# APD9328_FPGA_SUPPLY.net
KiCad netlist of a schematic drawn in Altium Designer
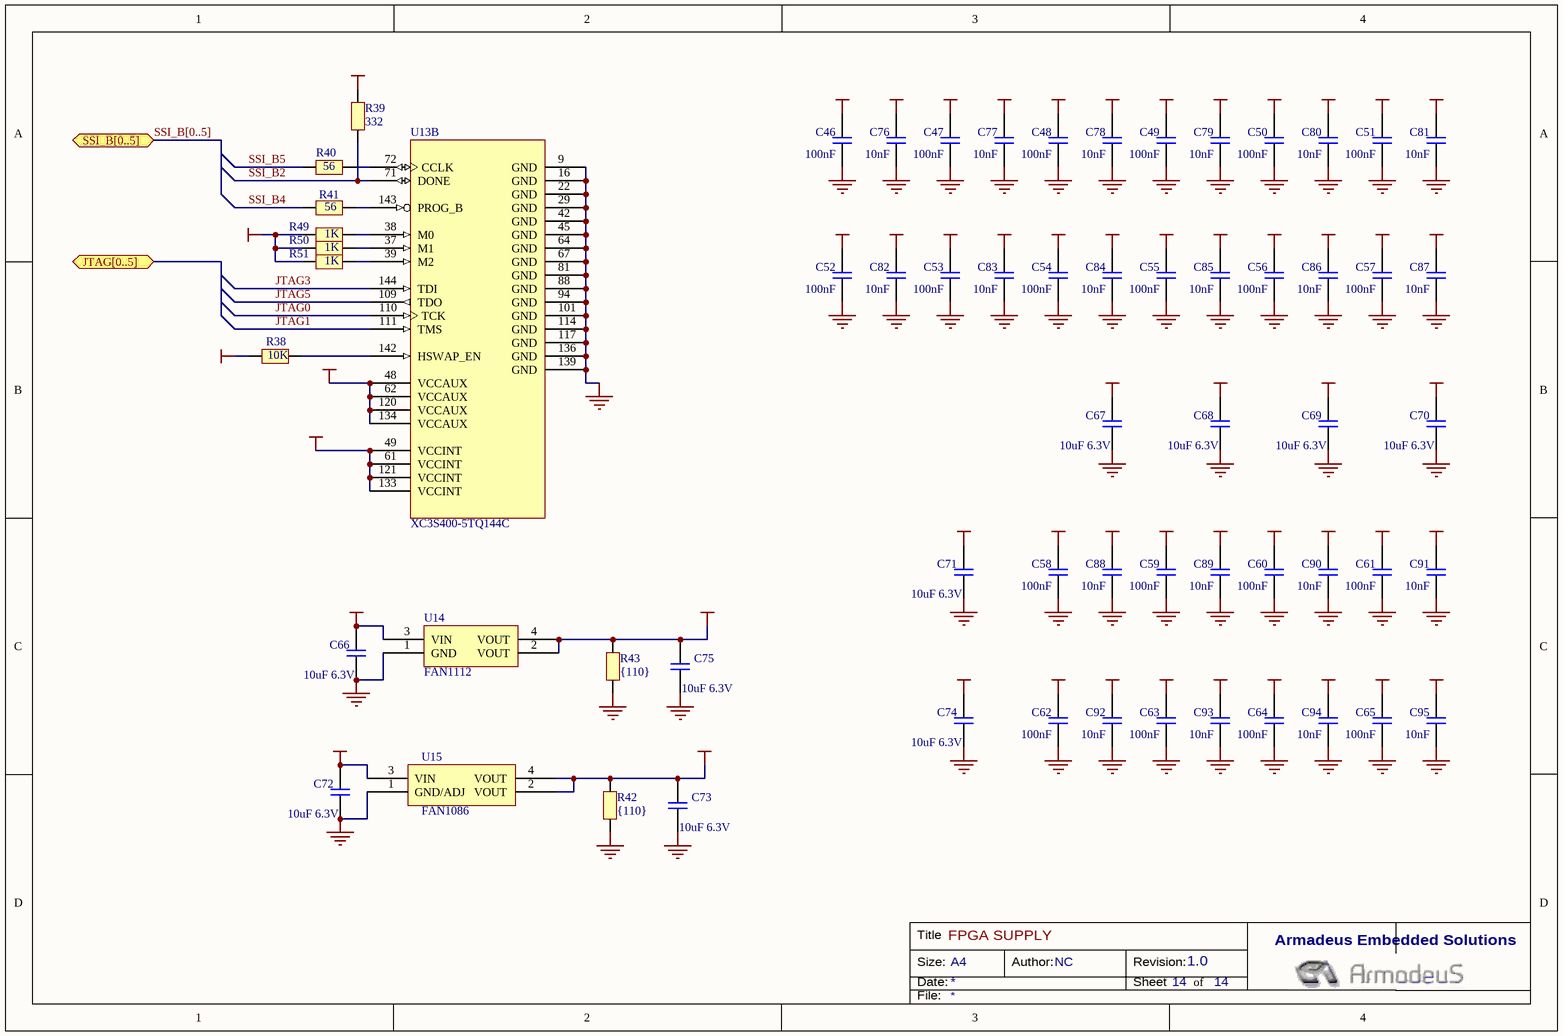
[diagram p0: APD9328_FPGA_SUPPLY.SchDoc]

(export (version "E")
  (design (tool "Eeschema 10.0.6"))
  (components
    (comp (ref "C46") (value "100nF") (footprint "0402") (libsource (lib "*") (part "Cap")))
    (comp (ref "C47") (value "100nF") (footprint "0402") (libsource (lib "*") (part "Cap")))
    (comp (ref "C48") (value "100nF") (footprint "0402") (libsource (lib "*") (part "Cap")))
    (comp (ref "C49") (value "100nF") (footprint "0402") (libsource (lib "*") (part "Cap")))
    (comp (ref "C50") (value "100nF") (footprint "0402") (libsource (lib "*") (part "Cap")))
    (comp (ref "C51") (value "100nF") (footprint "0402") (libsource (lib "*") (part "Cap")))
    (comp (ref "C52") (value "100nF") (footprint "0402") (libsource (lib "*") (part "Cap")))
    (comp (ref "C53") (value "100nF") (footprint "0402") (libsource (lib "*") (part "Cap")))
    (comp (ref "C54") (value "100nF") (footprint "0402") (libsource (lib "*") (part "Cap")))
    (comp (ref "C55") (value "100nF") (footprint "0402") (libsource (lib "*") (part "Cap")))
    (comp (ref "C56") (value "100nF") (footprint "0402") (libsource (lib "*") (part "Cap")))
    (comp (ref "C57") (value "100nF") (footprint "0402") (libsource (lib "*") (part "Cap")))
    (comp (ref "C58") (value "100nF") (footprint "0402") (libsource (lib "*") (part "Cap")))
    (comp (ref "C59") (value "100nF") (footprint "0402") (libsource (lib "*") (part "Cap")))
    (comp (ref "C60") (value "100nF") (footprint "0402") (libsource (lib "*") (part "Cap")))
    (comp (ref "C61") (value "100nF") (footprint "0402") (libsource (lib "*") (part "Cap")))
    (comp (ref "C62") (value "100nF") (footprint "0402") (libsource (lib "*") (part "Cap")))
    (comp (ref "C63") (value "100nF") (footprint "0402") (libsource (lib "*") (part "Cap")))
    (comp (ref "C64") (value "100nF") (footprint "0402") (libsource (lib "*") (part "Cap")))
    (comp (ref "C65") (value "100nF") (footprint "0402") (libsource (lib "*") (part "Cap")))
    (comp (ref "C66")
      (value "10uF 6.3V")
      (footprint "0805")
      (description "Ceramic Capacitor")
      (libsource (lib "*") (part "Cap"))
    )
    (comp (ref "C67")
      (value "10uF 6.3V")
      (footprint "0805")
      (description "Ceramic Capacitor")
      (libsource (lib "*") (part "Cap"))
    )
    (comp (ref "C68")
      (value "10uF 6.3V")
      (footprint "0805")
      (description "Ceramic Capacitor")
      (libsource (lib "*") (part "Cap"))
    )
    (comp (ref "C69")
      (value "10uF 6.3V")
      (footprint "0805")
      (description "Ceramic Capacitor")
      (libsource (lib "*") (part "Cap"))
    )
    (comp (ref "C70")
      (value "10uF 6.3V")
      (footprint "0805")
      (description "Ceramic Capacitor")
      (libsource (lib "*") (part "Cap"))
    )
    (comp (ref "C71")
      (value "10uF 6.3V")
      (footprint "0805")
      (description "Ceramic Capacitor")
      (libsource (lib "*") (part "Cap"))
    )
    (comp (ref "C72")
      (value "10uF 6.3V")
      (footprint "0805")
      (description "Ceramic Capacitor")
      (libsource (lib "*") (part "Cap"))
    )
    (comp (ref "C73")
      (value "10uF 6.3V")
      (footprint "0805")
      (description "Ceramic Capacitor")
      (libsource (lib "*") (part "Cap"))
    )
    (comp (ref "C74")
      (value "10uF 6.3V")
      (footprint "0805")
      (description "Ceramic Capacitor")
      (libsource (lib "*") (part "Cap"))
    )
    (comp (ref "C75")
      (value "10uF 6.3V")
      (footprint "0805")
      (description "Ceramic Capacitor")
      (libsource (lib "*") (part "Cap"))
    )
    (comp (ref "C76")
      (value "10nF")
      (footprint "0402")
      (fields (field (name "MANUFACTURER") "Kemet") (field (name "PART NUMBER") "C0402C103K4RACTU"))
      (libsource (lib "*") (part "Cap"))
    )
    (comp (ref "C77") (value "10nF") (footprint "0402") (libsource (lib "*") (part "Cap")))
    (comp (ref "C78") (value "10nF") (footprint "0402") (libsource (lib "*") (part "Cap")))
    (comp (ref "C79") (value "10nF") (footprint "0402") (libsource (lib "*") (part "Cap")))
    (comp (ref "C80") (value "10nF") (footprint "0402") (libsource (lib "*") (part "Cap")))
    (comp (ref "C81") (value "10nF") (footprint "0402") (libsource (lib "*") (part "Cap")))
    (comp (ref "C82") (value "10nF") (footprint "0402") (libsource (lib "*") (part "Cap")))
    (comp (ref "C83") (value "10nF") (footprint "0402") (libsource (lib "*") (part "Cap")))
    (comp (ref "C84") (value "10nF") (footprint "0402") (libsource (lib "*") (part "Cap")))
    (comp (ref "C85") (value "10nF") (footprint "0402") (libsource (lib "*") (part "Cap")))
    (comp (ref "C86") (value "10nF") (footprint "0402") (libsource (lib "*") (part "Cap")))
    (comp (ref "C87") (value "10nF") (footprint "0402") (libsource (lib "*") (part "Cap")))
    (comp (ref "C88") (value "10nF") (footprint "0402") (libsource (lib "*") (part "Cap")))
    (comp (ref "C89") (value "10nF") (footprint "0402") (libsource (lib "*") (part "Cap")))
    (comp (ref "C90") (value "10nF") (footprint "0402") (libsource (lib "*") (part "Cap")))
    (comp (ref "C91") (value "10nF") (footprint "0402") (libsource (lib "*") (part "Cap")))
    (comp (ref "C92") (value "10nF") (footprint "0402") (libsource (lib "*") (part "Cap")))
    (comp (ref "C93") (value "10nF") (footprint "0402") (libsource (lib "*") (part "Cap")))
    (comp (ref "C94") (value "10nF") (footprint "0402") (libsource (lib "*") (part "Cap")))
    (comp (ref "C95") (value "10nF") (footprint "0402") (libsource (lib "*") (part "Cap")))
    (comp (ref "R38") (value "10K") (footprint "0402") (libsource (lib "") (part "Res_1")))
    (comp (ref "R39") (value "332") (footprint "0402") (libsource (lib "*") (part "Res")))
    (comp (ref "R40") (value "56") (footprint "0402") (libsource (lib "") (part "Res_1")))
    (comp (ref "R41") (value "56") (footprint "0402") (libsource (lib "") (part "Res_1")))
    (comp (ref "R42") (value "{110}") (footprint "0402") (libsource (lib "*") (part "Res")))
    (comp (ref "R43") (value "{110}") (footprint "0402") (libsource (lib "*") (part "Res")))
    (comp (ref "R49") (value "1K") (footprint "0402") (libsource (lib "") (part "Res_1")))
    (comp (ref "R50") (value "1K") (footprint "0402") (libsource (lib "") (part "Res_1")))
    (comp (ref "R51") (value "1K") (footprint "0402") (libsource (lib "") (part "Res_1")))
    (comp (ref "U13")
      (value "XC3S400-5TQ144C")
      (footprint "TQ144")
      (description "Spartan-3 1.2V FPGA, 97 User I/Os, 144-pin TQFP, High Performance, Commercial Grade")
      (fields (field (name "PUBLISHER") "Altium Limited"))
      (libsource (lib "Xilinx Spartan-3") (part "XC3S400-5TQ144C"))
    )
    (comp (ref "U14")
      (value "FAN1112")
      (footprint "SOT223")
      (description "Linear Regulator")
      (fields (field (name "MANUFACTURER") "Fairchild") (field (name "PART NUMBER") "FAN1112SX"))
      (libsource (lib "*") (part "FAN1112"))
    )
    (comp (ref "U15") (value "FAN1086") (footprint "SOT223") (libsource (lib "Armadeus") (part "FAN1086")))
  )
  (nets
    (net (code "6") (name "+1V2") (class "Default")
      (node (ref "C62") (pin "2") (pintype "passive"))
      (node (ref "C63") (pin "2") (pintype "passive"))
      (node (ref "C64") (pin "2") (pintype "passive"))
      (node (ref "C65") (pin "2") (pintype "passive"))
      (node (ref "C74") (pin "2") (pintype "passive"))
      (node (ref "C75") (pin "2") (pintype "passive"))
      (node (ref "C92") (pin "2") (pintype "passive"))
      (node (ref "C93") (pin "2") (pintype "passive"))
      (node (ref "C94") (pin "2") (pintype "passive"))
      (node (ref "C95") (pin "2") (pintype "passive"))
      (node (ref "R43") (pin "2") (pintype "passive"))
      (node (ref "U13") (pin "121") (pinfunction "VCCINT_121") (pintype "power_in"))
      (node (ref "U13") (pin "133") (pinfunction "VCCINT_133") (pintype "power_in"))
      (node (ref "U13") (pin "49") (pinfunction "VCCINT_49") (pintype "power_in"))
      (node (ref "U13") (pin "61") (pinfunction "VCCINT_61") (pintype "power_in"))
      (node (ref "U14") (pin "2") (pinfunction "VOUT_2") (pintype "power_in"))
      (node (ref "U14") (pin "4") (pinfunction "VOUT_4") (pintype "power_in"))
    )
    (net (code "7") (name "+2V5") (class "Default")
      (node (ref "C58") (pin "2") (pintype "passive"))
      (node (ref "C59") (pin "2") (pintype "passive"))
      (node (ref "C60") (pin "2") (pintype "passive"))
      (node (ref "C61") (pin "2") (pintype "passive"))
      (node (ref "C66") (pin "2") (pintype "passive"))
      (node (ref "C71") (pin "2") (pintype "passive"))
      (node (ref "C73") (pin "2") (pintype "passive"))
      (node (ref "C88") (pin "2") (pintype "passive"))
      (node (ref "C89") (pin "2") (pintype "passive"))
      (node (ref "C90") (pin "2") (pintype "passive"))
      (node (ref "C91") (pin "2") (pintype "passive"))
      (node (ref "R38") (pin "1") (pintype "passive"))
      (node (ref "R39") (pin "2") (pintype "passive"))
      (node (ref "R42") (pin "2") (pintype "passive"))
      (node (ref "R49") (pin "1") (pintype "passive"))
      (node (ref "R50") (pin "1") (pintype "passive"))
      (node (ref "R51") (pin "1") (pintype "passive"))
      (node (ref "U13") (pin "120") (pinfunction "VCCAUX_120") (pintype "power_in"))
      (node (ref "U13") (pin "134") (pinfunction "VCCAUX_134") (pintype "power_in"))
      (node (ref "U13") (pin "48") (pinfunction "VCCAUX_48") (pintype "power_in"))
      (node (ref "U13") (pin "62") (pinfunction "VCCAUX_62") (pintype "power_in"))
      (node (ref "U14") (pin "3") (pinfunction "VIN_3") (pintype "power_in"))
      (node (ref "U15") (pin "2") (pinfunction "VOUT_2") (pintype "power_in"))
      (node (ref "U15") (pin "4") (pinfunction "VOUT_4") (pintype "power_in"))
    )
    (net (code "8") (name "+3V3") (class "Default")
      (node (ref "C46") (pin "2") (pintype "passive"))
      (node (ref "C47") (pin "2") (pintype "passive"))
      (node (ref "C48") (pin "2") (pintype "passive"))
      (node (ref "C49") (pin "2") (pintype "passive"))
      (node (ref "C50") (pin "2") (pintype "passive"))
      (node (ref "C51") (pin "2") (pintype "passive"))
      (node (ref "C52") (pin "2") (pintype "passive"))
      (node (ref "C53") (pin "2") (pintype "passive"))
      (node (ref "C54") (pin "2") (pintype "passive"))
      (node (ref "C55") (pin "2") (pintype "passive"))
      (node (ref "C56") (pin "2") (pintype "passive"))
      (node (ref "C57") (pin "2") (pintype "passive"))
      (node (ref "C67") (pin "2") (pintype "passive"))
      (node (ref "C68") (pin "2") (pintype "passive"))
      (node (ref "C69") (pin "2") (pintype "passive"))
      (node (ref "C70") (pin "2") (pintype "passive"))
      (node (ref "C72") (pin "2") (pintype "passive"))
      (node (ref "C76") (pin "2") (pintype "passive"))
      (node (ref "C77") (pin "2") (pintype "passive"))
      (node (ref "C78") (pin "2") (pintype "passive"))
      (node (ref "C79") (pin "2") (pintype "passive"))
      (node (ref "C80") (pin "2") (pintype "passive"))
      (node (ref "C81") (pin "2") (pintype "passive"))
      (node (ref "C82") (pin "2") (pintype "passive"))
      (node (ref "C83") (pin "2") (pintype "passive"))
      (node (ref "C84") (pin "2") (pintype "passive"))
      (node (ref "C85") (pin "2") (pintype "passive"))
      (node (ref "C86") (pin "2") (pintype "passive"))
      (node (ref "C87") (pin "2") (pintype "passive"))
      (node (ref "U15") (pin "3") (pinfunction "VIN_3") (pintype "power_in"))
    )
    (net (code "9") (name "/JTAG0") (class "Default")
      (node (ref "U13") (pin "110") (pinfunction "TCK_110") (pintype "input"))
    )
    (net (code "10") (name "/JTAG1") (class "Default")
      (node (ref "U13") (pin "111") (pinfunction "TMS_111") (pintype "input"))
    )
    (net (code "11") (name "/JTAG3") (class "Default")
      (node (ref "U13") (pin "144") (pinfunction "TDI_144") (pintype "input"))
    )
    (net (code "12") (name "/JTAG5") (class "Default")
      (node (ref "U13") (pin "109") (pinfunction "TDO_109") (pintype "output"))
    )
    (net (code "14") (name "/SSI_B2") (class "Default")
      (node (ref "R39") (pin "1") (pintype "passive"))
      (node (ref "U13") (pin "71") (pinfunction "DONE_71") (pintype "bidirectional"))
    )
    (net (code "15") (name "/SSI_B4") (class "Default") (node (ref "R41") (pin "1") (pintype "passive")))
    (net (code "16") (name "/SSI_B5") (class "Default") (node (ref "R40") (pin "1") (pintype "passive")))
    (net (code "18") (name "GND") (class "Default")
      (node (ref "C46") (pin "1") (pintype "passive"))
      (node (ref "C47") (pin "1") (pintype "passive"))
      (node (ref "C48") (pin "1") (pintype "passive"))
      (node (ref "C49") (pin "1") (pintype "passive"))
      (node (ref "C50") (pin "1") (pintype "passive"))
      (node (ref "C51") (pin "1") (pintype "passive"))
      (node (ref "C52") (pin "1") (pintype "passive"))
      (node (ref "C53") (pin "1") (pintype "passive"))
      (node (ref "C54") (pin "1") (pintype "passive"))
      (node (ref "C55") (pin "1") (pintype "passive"))
      (node (ref "C56") (pin "1") (pintype "passive"))
      (node (ref "C57") (pin "1") (pintype "passive"))
      (node (ref "C58") (pin "1") (pintype "passive"))
      (node (ref "C59") (pin "1") (pintype "passive"))
      (node (ref "C60") (pin "1") (pintype "passive"))
      (node (ref "C61") (pin "1") (pintype "passive"))
      (node (ref "C62") (pin "1") (pintype "passive"))
      (node (ref "C63") (pin "1") (pintype "passive"))
      (node (ref "C64") (pin "1") (pintype "passive"))
      (node (ref "C65") (pin "1") (pintype "passive"))
      (node (ref "C66") (pin "1") (pintype "passive"))
      (node (ref "C67") (pin "1") (pintype "passive"))
      (node (ref "C68") (pin "1") (pintype "passive"))
      (node (ref "C69") (pin "1") (pintype "passive"))
      (node (ref "C70") (pin "1") (pintype "passive"))
      (node (ref "C71") (pin "1") (pintype "passive"))
      (node (ref "C72") (pin "1") (pintype "passive"))
      (node (ref "C73") (pin "1") (pintype "passive"))
      (node (ref "C74") (pin "1") (pintype "passive"))
      (node (ref "C75") (pin "1") (pintype "passive"))
      (node (ref "C76") (pin "1") (pintype "passive"))
      (node (ref "C77") (pin "1") (pintype "passive"))
      (node (ref "C78") (pin "1") (pintype "passive"))
      (node (ref "C79") (pin "1") (pintype "passive"))
      (node (ref "C80") (pin "1") (pintype "passive"))
      (node (ref "C81") (pin "1") (pintype "passive"))
      (node (ref "C82") (pin "1") (pintype "passive"))
      (node (ref "C83") (pin "1") (pintype "passive"))
      (node (ref "C84") (pin "1") (pintype "passive"))
      (node (ref "C85") (pin "1") (pintype "passive"))
      (node (ref "C86") (pin "1") (pintype "passive"))
      (node (ref "C87") (pin "1") (pintype "passive"))
      (node (ref "C88") (pin "1") (pintype "passive"))
      (node (ref "C89") (pin "1") (pintype "passive"))
      (node (ref "C90") (pin "1") (pintype "passive"))
      (node (ref "C91") (pin "1") (pintype "passive"))
      (node (ref "C92") (pin "1") (pintype "passive"))
      (node (ref "C93") (pin "1") (pintype "passive"))
      (node (ref "C94") (pin "1") (pintype "passive"))
      (node (ref "C95") (pin "1") (pintype "passive"))
      (node (ref "R42") (pin "1") (pintype "passive"))
      (node (ref "R43") (pin "1") (pintype "passive"))
      (node (ref "U13") (pin "101") (pinfunction "GND_101") (pintype "power_in"))
      (node (ref "U13") (pin "114") (pinfunction "GND_114") (pintype "power_in"))
      (node (ref "U13") (pin "117") (pinfunction "GND_117") (pintype "power_in"))
      (node (ref "U13") (pin "136") (pinfunction "GND_136") (pintype "power_in"))
      (node (ref "U13") (pin "139") (pinfunction "GND_139") (pintype "power_in"))
      (node (ref "U13") (pin "16") (pinfunction "GND_16") (pintype "power_in"))
      (node (ref "U13") (pin "22") (pinfunction "GND_22") (pintype "power_in"))
      (node (ref "U13") (pin "29") (pinfunction "GND_29") (pintype "power_in"))
      (node (ref "U13") (pin "42") (pinfunction "GND_42") (pintype "power_in"))
      (node (ref "U13") (pin "45") (pinfunction "GND_45") (pintype "power_in"))
      (node (ref "U13") (pin "64") (pinfunction "GND_64") (pintype "power_in"))
      (node (ref "U13") (pin "67") (pinfunction "GND_67") (pintype "power_in"))
      (node (ref "U13") (pin "81") (pinfunction "GND_81") (pintype "power_in"))
      (node (ref "U13") (pin "88") (pinfunction "GND_88") (pintype "power_in"))
      (node (ref "U13") (pin "9") (pinfunction "GND_9") (pintype "power_in"))
      (node (ref "U13") (pin "94") (pinfunction "GND_94") (pintype "power_in"))
      (node (ref "U14") (pin "1") (pinfunction "GND_1") (pintype "power_in"))
      (node (ref "U15") (pin "1") (pinfunction "GND/ADJ_1") (pintype "power_in"))
    )
    (net (code "19") (name "Net-(U13B-CCLK)") (class "Default")
      (node (ref "R40") (pin "2") (pintype "passive"))
      (node (ref "U13") (pin "72") (pinfunction "CCLK_72") (pintype "bidirectional"))
    )
    (net (code "20") (name "Net-(U13B-HSWAP_EN)") (class "Default")
      (node (ref "R38") (pin "2") (pintype "passive"))
      (node (ref "U13") (pin "142") (pinfunction "HSWAP_EN_142") (pintype "input"))
    )
    (net (code "21") (name "Net-(U13B-M0)") (class "Default")
      (node (ref "R49") (pin "2") (pintype "passive"))
      (node (ref "U13") (pin "38") (pinfunction "M0_38") (pintype "input"))
    )
    (net (code "22") (name "Net-(U13B-M1)") (class "Default")
      (node (ref "R50") (pin "2") (pintype "passive"))
      (node (ref "U13") (pin "37") (pinfunction "M1_37") (pintype "input"))
    )
    (net (code "23") (name "Net-(U13B-M2)") (class "Default")
      (node (ref "R51") (pin "2") (pintype "passive"))
      (node (ref "U13") (pin "39") (pinfunction "M2_39") (pintype "input"))
    )
    (net (code "24") (name "Net-(U13B-PROG_B)") (class "Default")
      (node (ref "R41") (pin "2") (pintype "passive"))
      (node (ref "U13") (pin "143") (pinfunction "PROG_B_143") (pintype "input"))
    )
  )
)
